# ray.net
KiCad netlist of a schematic drawn in EAGLE
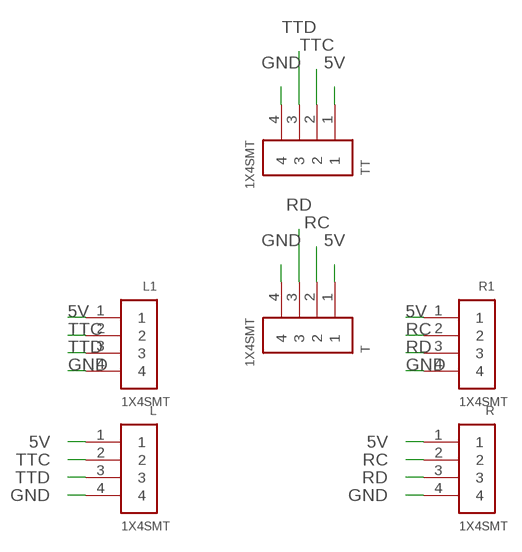
[diagram p0: schematic, sheet 1]

(export (version "E")
  (design (tool "Eeschema 10.0.6"))
  (components
    (comp (ref "L")
      (value "1X4SMT")
      (footprint "eagle-import:1X4-SMT")
      (libsource (lib "eagle-import") (part "1X4SMT"))
    )
    (comp (ref "L1")
      (value "1X4SMT")
      (footprint "eagle-import:1X4-SMT")
      (libsource (lib "eagle-import") (part "1X4SMT"))
    )
    (comp (ref "R")
      (value "1X4SMT")
      (footprint "eagle-import:1X4-SMT")
      (libsource (lib "eagle-import") (part "1X4SMT"))
    )
    (comp (ref "R1")
      (value "1X4SMT")
      (footprint "eagle-import:1X4-SMT")
      (libsource (lib "eagle-import") (part "1X4SMT"))
    )
    (comp (ref "T")
      (value "1X4SMT")
      (footprint "eagle-import:1X4-SMT")
      (libsource (lib "eagle-import") (part "1X4SMT"))
    )
    (comp (ref "TT")
      (value "1X4SMT")
      (footprint "eagle-import:1X4-SMT")
      (libsource (lib "eagle-import") (part "1X4SMT"))
    )
  )
  (nets
    (net (code "1") (name "/5V") (class "Default")
      (node (ref "L") (pin "1") (pinfunction "1_1") (pintype "bidirectional"))
      (node (ref "L1") (pin "1") (pinfunction "1_1") (pintype "bidirectional"))
      (node (ref "R") (pin "1") (pinfunction "1_1") (pintype "bidirectional"))
      (node (ref "R1") (pin "1") (pinfunction "1_1") (pintype "bidirectional"))
      (node (ref "T") (pin "1") (pinfunction "1_1") (pintype "bidirectional"))
      (node (ref "TT") (pin "1") (pinfunction "1_1") (pintype "bidirectional"))
    )
    (net (code "2") (name "/GND") (class "Default")
      (node (ref "L") (pin "4") (pinfunction "4_4") (pintype "bidirectional"))
      (node (ref "L1") (pin "4") (pinfunction "4_4") (pintype "bidirectional"))
      (node (ref "R") (pin "4") (pinfunction "4_4") (pintype "bidirectional"))
      (node (ref "R1") (pin "4") (pinfunction "4_4") (pintype "bidirectional"))
      (node (ref "T") (pin "4") (pinfunction "4_4") (pintype "bidirectional"))
      (node (ref "TT") (pin "4") (pinfunction "4_4") (pintype "bidirectional"))
    )
    (net (code "3") (name "/RC") (class "Default")
      (node (ref "R") (pin "2") (pinfunction "2_2") (pintype "bidirectional"))
      (node (ref "R1") (pin "2") (pinfunction "2_2") (pintype "bidirectional"))
      (node (ref "T") (pin "2") (pinfunction "2_2") (pintype "bidirectional"))
    )
    (net (code "4") (name "/RD") (class "Default")
      (node (ref "R") (pin "3") (pinfunction "3_3") (pintype "bidirectional"))
      (node (ref "R1") (pin "3") (pinfunction "3_3") (pintype "bidirectional"))
      (node (ref "T") (pin "3") (pinfunction "3_3") (pintype "bidirectional"))
    )
    (net (code "5") (name "/TTC") (class "Default")
      (node (ref "L") (pin "2") (pinfunction "2_2") (pintype "bidirectional"))
      (node (ref "L1") (pin "2") (pinfunction "2_2") (pintype "bidirectional"))
      (node (ref "TT") (pin "2") (pinfunction "2_2") (pintype "bidirectional"))
    )
    (net (code "6") (name "/TTD") (class "Default")
      (node (ref "L") (pin "3") (pinfunction "3_3") (pintype "bidirectional"))
      (node (ref "L1") (pin "3") (pinfunction "3_3") (pintype "bidirectional"))
      (node (ref "TT") (pin "3") (pinfunction "3_3") (pintype "bidirectional"))
    )
  )
)
